# controller_board3.net
KiCad netlist of a schematic drawn in EAGLE
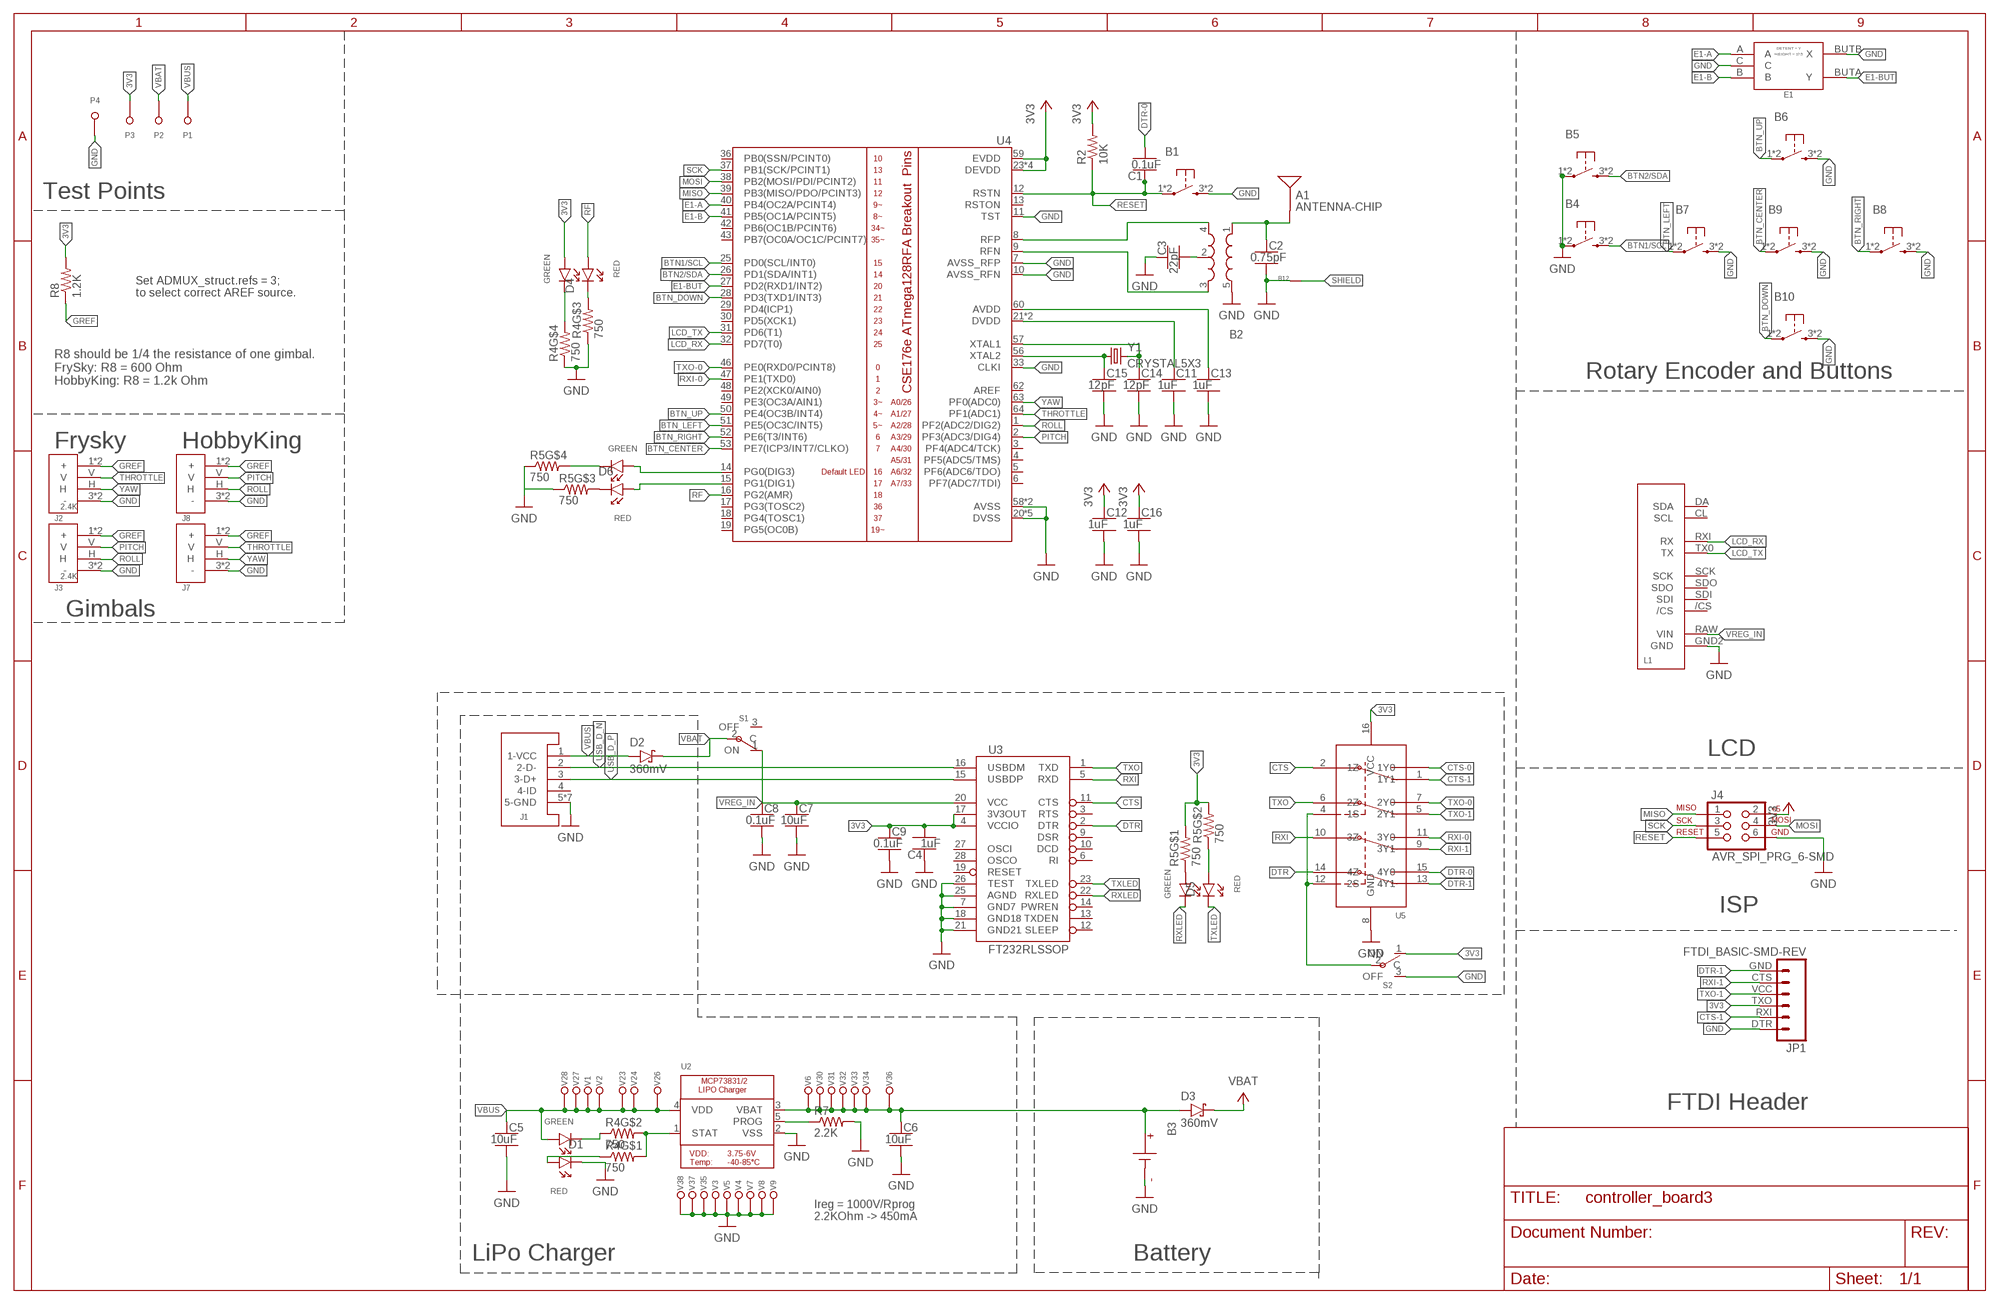
[diagram p0: schematic, sheet 1]

(export (version "E")
  (design (tool "Eeschema 10.0.6"))
  (components
    (comp (ref "A1")
      (value "ANTENNA-CHIP")
      (footprint "eagle-import:ANTENNA-CHIP")
      (fields
        (field (name "MFR") "Linx Technologies Inc.")
        (field (name "MPN") "ANT-2.45-CHP-T")
        (field (name "CREATOR") "Swanson")
        (field (name "REVIEWER") "Swanson")
      )
      (libsource (lib "eagle-import") (part "ANTENNA-CHIP"))
    )
    (comp (ref "B1")
      (value "PUSHBUTTON_-4.5X4.5")
      (footprint "eagle-import:4.5MM_TACTILE_SWITCH_TL3305AF160QG")
      (fields (field (name "CREATOR") "Swanson"))
      (libsource (lib "eagle-import") (part "PUSHBUTTON_-4.5X4.5"))
    )
    (comp (ref "B2")
      (value "BALUN0805")
      (footprint "eagle-import:BALUN")
      (fields
        (field (name "MFR") "Wurth Electronics Inc")
        (field (name "MPN") "748421245")
        (field (name "CREATOR") "Swanson")
        (field (name "REVIEWER") "Swanson")
      )
      (libsource (lib "eagle-import") (part "BALUN0805"))
    )
    (comp (ref "B3")
      (value "BATTERY")
      (footprint "eagle-import:BATTERY-TERMINALS")
      (fields (field (name "CREATOR") "Swanson"))
      (libsource (lib "eagle-import") (part "BATTERY"))
    )
    (comp (ref "B4")
      (value "PUSHBUTTON_-4.5X4.5")
      (footprint "eagle-import:4.5MM_TACTILE_SWITCH_TL3305AF160QG")
      (fields (field (name "CREATOR") "Swanson"))
      (libsource (lib "eagle-import") (part "PUSHBUTTON_-4.5X4.5"))
    )
    (comp (ref "B5")
      (value "PUSHBUTTON_-4.5X4.5")
      (footprint "eagle-import:4.5MM_TACTILE_SWITCH_TL3305AF160QG")
      (fields (field (name "CREATOR") "Swanson"))
      (libsource (lib "eagle-import") (part "PUSHBUTTON_-4.5X4.5"))
    )
    (comp (ref "B6")
      (value "PUSHBUTTON_-4.5X4.5")
      (footprint "eagle-import:4.5MM_TACTILE_SWITCH_TL3305AF160QG")
      (fields (field (name "CREATOR") "Swanson"))
      (libsource (lib "eagle-import") (part "PUSHBUTTON_-4.5X4.5"))
    )
    (comp (ref "B7")
      (value "PUSHBUTTON_-4.5X4.5")
      (footprint "eagle-import:4.5MM_TACTILE_SWITCH_TL3305AF160QG")
      (fields (field (name "CREATOR") "Swanson"))
      (libsource (lib "eagle-import") (part "PUSHBUTTON_-4.5X4.5"))
    )
    (comp (ref "B8")
      (value "PUSHBUTTON_-4.5X4.5")
      (footprint "eagle-import:4.5MM_TACTILE_SWITCH_TL3305AF160QG")
      (fields (field (name "CREATOR") "Swanson"))
      (libsource (lib "eagle-import") (part "PUSHBUTTON_-4.5X4.5"))
    )
    (comp (ref "B9")
      (value "PUSHBUTTON_-4.5X4.5")
      (footprint "eagle-import:4.5MM_TACTILE_SWITCH_TL3305AF160QG")
      (fields (field (name "CREATOR") "Swanson"))
      (libsource (lib "eagle-import") (part "PUSHBUTTON_-4.5X4.5"))
    )
    (comp (ref "B10")
      (value "PUSHBUTTON_-4.5X4.5")
      (footprint "eagle-import:4.5MM_TACTILE_SWITCH_TL3305AF160QG")
      (fields (field (name "CREATOR") "Swanson"))
      (libsource (lib "eagle-import") (part "PUSHBUTTON_-4.5X4.5"))
    )
    (comp (ref "B12")
      (value "NET_BRIDGE")
      (footprint "eagle-import:NET_BRIDGE")
      (fields (field (name "CREATOR") "Michael Gonzalez"))
      (libsource (lib "eagle-import") (part "NET_BRIDGE"))
    )
    (comp (ref "C1")
      (value "0.1uF")
      (footprint "eagle-import:CAPC2012X140_HS")
      (fields
        (field (name "MFR") "TDK")
        (field (name "MPN") "C2012X7R2A104K125AA")
        (field (name "CREATOR") "Swanson")
        (field (name "REVIEWER") "Swanson")
      )
      (libsource (lib "eagle-import") (part "CAPACITOR-NP_SMD-2012-0805_CERAMIC-0.1UF"))
    )
    (comp (ref "C2")
      (value "0.75pF")
      (footprint "eagle-import:CAPC2012X140_HS")
      (fields
        (field (name "MFR") "Murata Electronics North America")
        (field (name "MPN") "GQM2195C2AR75CB01D")
        (field (name "CREATOR") "Swanson")
        (field (name "REVIEWER") "Swanson")
      )
      (libsource (lib "eagle-import") (part "CAPACITOR-NP_SMD-2012-0805_CERAMIC-0.75PF"))
    )
    (comp (ref "C3")
      (value "22pF")
      (footprint "eagle-import:CAPC2012X140_HS")
      (fields
        (field (name "MFR") "Murata Electronics North America")
        (field (name "MPN") "GRM21A5C2E220JW01D")
        (field (name "CREATOR") "Swanson")
        (field (name "REVIEWER") "Swanson")
      )
      (libsource (lib "eagle-import") (part "CAPACITOR-NP_SMD-2012-0805_CERAMIC-22PF"))
    )
    (comp (ref "C4")
      (value "1uF")
      (footprint "eagle-import:CAPC2012X140_HS")
      (fields
        (field (name "MFR") "Taiyo Yuden")
        (field (name "MPN") "TMK212B7105KG-T")
        (field (name "CREATOR") "Swanson")
        (field (name "REVIEWER") "Swanson")
      )
      (libsource (lib "eagle-import") (part "CAPACITOR-NP_SMD-2012-0805_CERAMIC-1UF"))
    )
    (comp (ref "C5")
      (value "10uF")
      (footprint "eagle-import:CAPC1608X100")
      (fields (field (name "CREATOR") "Swanson"))
      (libsource (lib "eagle-import") (part "CAPACITOR-NP_SMD-0603_CERAMIC-10UF"))
    )
    (comp (ref "C6")
      (value "10uF")
      (footprint "eagle-import:CAPC1608X100")
      (fields (field (name "CREATOR") "Swanson"))
      (libsource (lib "eagle-import") (part "CAPACITOR-NP_SMD-0603_CERAMIC-10UF"))
    )
    (comp (ref "C7")
      (value "10uF")
      (footprint "eagle-import:CAPC1608X100")
      (fields (field (name "CREATOR") "Swanson"))
      (libsource (lib "eagle-import") (part "CAPACITOR-NP_SMD-0603_CERAMIC-10UF"))
    )
    (comp (ref "C8")
      (value "0.1uF")
      (footprint "eagle-import:CAPC2012X140_HS")
      (fields
        (field (name "MFR") "TDK")
        (field (name "MPN") "C2012X7R2A104K125AA")
        (field (name "CREATOR") "Swanson")
        (field (name "REVIEWER") "Swanson")
      )
      (libsource (lib "eagle-import") (part "CAPACITOR-NP_SMD-2012-0805_CERAMIC-0.1UF"))
    )
    (comp (ref "C9")
      (value "0.1uF")
      (footprint "eagle-import:CAPC2012X140_HS")
      (fields
        (field (name "MFR") "TDK")
        (field (name "MPN") "C2012X7R2A104K125AA")
        (field (name "CREATOR") "Swanson")
        (field (name "REVIEWER") "Swanson")
      )
      (libsource (lib "eagle-import") (part "CAPACITOR-NP_SMD-2012-0805_CERAMIC-0.1UF"))
    )
    (comp (ref "C11")
      (value "1uF")
      (footprint "eagle-import:CAPC2012X140_HS")
      (fields
        (field (name "MFR") "Taiyo Yuden")
        (field (name "MPN") "TMK212B7105KG-T")
        (field (name "CREATOR") "Swanson")
        (field (name "REVIEWER") "Swanson")
      )
      (libsource (lib "eagle-import") (part "CAPACITOR-NP_SMD-2012-0805_CERAMIC-1UF"))
    )
    (comp (ref "C12")
      (value "1uF")
      (footprint "eagle-import:CAPC2012X140_HS")
      (fields
        (field (name "MFR") "Taiyo Yuden")
        (field (name "MPN") "TMK212B7105KG-T")
        (field (name "CREATOR") "Swanson")
        (field (name "REVIEWER") "Swanson")
      )
      (libsource (lib "eagle-import") (part "CAPACITOR-NP_SMD-2012-0805_CERAMIC-1UF"))
    )
    (comp (ref "C13")
      (value "1uF")
      (footprint "eagle-import:CAPC2012X140_HS")
      (fields
        (field (name "MFR") "Taiyo Yuden")
        (field (name "MPN") "TMK212B7105KG-T")
        (field (name "CREATOR") "Swanson")
        (field (name "REVIEWER") "Swanson")
      )
      (libsource (lib "eagle-import") (part "CAPACITOR-NP_SMD-2012-0805_CERAMIC-1UF"))
    )
    (comp (ref "C14")
      (value "12pF")
      (footprint "eagle-import:CAPC2012X140_HS")
      (fields
        (field (name "MFR") "Murata Electronics North America")
        (field (name "MPN") "GRM21A5C2E120JW01D")
        (field (name "CREATOR") "Swanson")
        (field (name "REVIEWER") "Swanson")
      )
      (libsource (lib "eagle-import") (part "CAPACITOR-NP_SMD-2012-0805_CERAMIC-12PF"))
    )
    (comp (ref "C15")
      (value "12pF")
      (footprint "eagle-import:CAPC2012X140_HS")
      (fields
        (field (name "MFR") "Murata Electronics North America")
        (field (name "MPN") "GRM21A5C2E120JW01D")
        (field (name "CREATOR") "Swanson")
        (field (name "REVIEWER") "Swanson")
      )
      (libsource (lib "eagle-import") (part "CAPACITOR-NP_SMD-2012-0805_CERAMIC-12PF"))
    )
    (comp (ref "C16")
      (value "1uF")
      (footprint "eagle-import:CAPC2012X140_HS")
      (fields
        (field (name "MFR") "Taiyo Yuden")
        (field (name "MPN") "TMK212B7105KG-T")
        (field (name "CREATOR") "Swanson")
        (field (name "REVIEWER") "Swanson")
      )
      (libsource (lib "eagle-import") (part "CAPACITOR-NP_SMD-2012-0805_CERAMIC-1UF"))
    )
    (comp (ref "D1")
      (value "LED-2X-GREEN/RED-1.6X1.5MM")
      (footprint "eagle-import:LED-2X-LITE-ON-1.6MMX1.5MM")
      (fields
        (field (name "COLOR2") "RED")
        (field (name "COLOR1") "GREEN")
        (field (name "CREATOR") "Swanson")
      )
      (libsource (lib "eagle-import") (part "LED-2X-GREEN/RED-1.6X1.5MM"))
    )
    (comp (ref "D2")
      (value "360mV")
      (footprint "eagle-import:SOD3716X135_HS")
      (fields
        (field (name "MFR") "Toshiba Semiconductor and Storage")
        (field (name "MPN") "CRS08(TE85L,Q,M)")
        (field (name "CREATOR") "Swanson")
        (field (name "REVIEWER") "Swanson")
      )
      (libsource (lib "eagle-import") (part "DIODE-SCHOTTKY_SMD-SOD123-360MV"))
    )
    (comp (ref "D3")
      (value "360mV")
      (footprint "eagle-import:SOD3716X135_HS")
      (fields
        (field (name "MFR") "Toshiba Semiconductor and Storage")
        (field (name "MPN") "CRS08(TE85L,Q,M)")
        (field (name "CREATOR") "Swanson")
        (field (name "REVIEWER") "Swanson")
      )
      (libsource (lib "eagle-import") (part "DIODE-SCHOTTKY_SMD-SOD123-360MV"))
    )
    (comp (ref "D4")
      (value "LED-2X-GREEN/RED-1.6X1.5MM")
      (footprint "eagle-import:LED-2X-LITE-ON-1.6MMX1.5MM")
      (fields
        (field (name "COLOR2") "RED")
        (field (name "COLOR1") "GREEN")
        (field (name "CREATOR") "Swanson")
      )
      (libsource (lib "eagle-import") (part "LED-2X-GREEN/RED-1.6X1.5MM"))
    )
    (comp (ref "D5")
      (value "LED-2X-GREEN/RED-1.6X1.5MM")
      (footprint "eagle-import:LED-2X-LITE-ON-1.6MMX1.5MM")
      (fields
        (field (name "COLOR2") "RED")
        (field (name "COLOR1") "GREEN")
        (field (name "CREATOR") "Swanson")
      )
      (libsource (lib "eagle-import") (part "LED-2X-GREEN/RED-1.6X1.5MM"))
    )
    (comp (ref "D6")
      (value "LED-2X-GREEN/RED-1.6X1.5MM")
      (footprint "eagle-import:LED-2X-LITE-ON-1.6MMX1.5MM")
      (fields
        (field (name "COLOR2") "RED")
        (field (name "COLOR1") "GREEN")
        (field (name "CREATOR") "Swanson")
      )
      (libsource (lib "eagle-import") (part "LED-2X-GREEN/RED-1.6X1.5MM"))
    )
    (comp (ref "E1")
      (value "ROTARY-ENCODER-W/BUTTON-BOURNS-PEC12R-4217F")
      (footprint "eagle-import:BOURNS-PEC12R")
      (fields (field (name "DETENT") "Y") (field (name "HEIGHT") "17.5") (field (name "CREATOR") "Swanson"))
      (libsource (lib "eagle-import") (part "ROTARY-ENCODER-W/BUTTON-BOURNS-PEC12R-4217F"))
    )
    (comp (ref "J1")
      (value "USB-MICROA-AMPHENOL-10118192-0001LF")
      (footprint "eagle-import:USB-MICROA-10118192-0001LF")
      (fields (field (name "CREATOR") "Swanson"))
      (libsource (lib "eagle-import") (part "USB-MICROA-AMPHENOL-10118192-0001LF"))
    )
    (comp (ref "J2")
      (value "2.4K")
      (footprint "eagle-import:JST-13-PTH")
      (fields (field (name "CREATOR") "Swanson"))
      (libsource (lib "eagle-import") (part "FRSKY-GIMBAL-FRYSKY"))
    )
    (comp (ref "J3")
      (value "2.4K")
      (footprint "eagle-import:JST-13-PTH")
      (fields (field (name "SPICEPREFIX") "E") (field (name "CREATOR") "Swanson"))
      (libsource (lib "eagle-import") (part "FRSKY-GIMBAL-FRYSKY"))
    )
    (comp (ref "J4")
      (value "AVR_SPI_PRG_6-SMD")
      (footprint "eagle-import:2X3-SMD")
      (fields (field (name "CREATOR") "Swanson"))
      (libsource (lib "eagle-import") (part "AVR_SPI_PRG_6-SMD"))
    )
    (comp (ref "J7")
      (value "FRSKY-GIMBAL-2X-SERVO-SMD")
      (footprint "eagle-import:2X-SERVO-SMD")
      (libsource (lib "eagle-import") (part "FRSKY-GIMBAL-2X-SERVO-SMD"))
    )
    (comp (ref "J8")
      (value "FRSKY-GIMBAL-2X-SERVO-SMD")
      (footprint "eagle-import:2X-SERVO-SMD")
      (libsource (lib "eagle-import") (part "FRSKY-GIMBAL-2X-SERVO-SMD"))
    )
    (comp (ref "JP1")
      (value "FTDI_BASIC-SMD-REV")
      (footprint "eagle-import:FTDI-BASIC-SMD")
      (libsource (lib "eagle-import") (part "FTDI_BASIC-SMD-REV"))
    )
    (comp (ref "L1")
      (value "SPARKFUN_SERLCD_SERIAL_REDUCED-SMD")
      (footprint "eagle-import:SPARKFUN_SERLCD_16X2_REDUCED_SMD")
      (fields (field (name "CREATOR") "Swanson"))
      (libsource (lib "eagle-import") (part "SPARKFUN_SERLCD_SERIAL_REDUCED-SMD"))
    )
    (comp (ref "P1")
      (value "TEST-POINT")
      (footprint "eagle-import:TEST-POINT-KEYSTONE-5000")
      (fields (field (name "CREATOR") "Swanson"))
      (libsource (lib "eagle-import") (part "TEST-POINT"))
    )
    (comp (ref "P2")
      (value "TEST-POINT")
      (footprint "eagle-import:TEST-POINT-KEYSTONE-5000")
      (fields (field (name "CREATOR") "Swanson"))
      (libsource (lib "eagle-import") (part "TEST-POINT"))
    )
    (comp (ref "P3")
      (value "TEST-POINT")
      (footprint "eagle-import:TEST-POINT-KEYSTONE-5000")
      (fields (field (name "CREATOR") "Swanson"))
      (libsource (lib "eagle-import") (part "TEST-POINT"))
    )
    (comp (ref "P4")
      (value "TEST-POINT")
      (footprint "eagle-import:TEST-POINT-KEYSTONE-5000")
      (fields (field (name "CREATOR") "Swanson"))
      (libsource (lib "eagle-import") (part "TEST-POINT"))
    )
    (comp (ref "R2")
      (value "10K")
      (footprint "eagle-import:RESC2012X60_HS")
      (fields
        (field (name "MFR") "Yageo")
        (field (name "MPN") "RC0805JR-0710KL")
        (field (name "CREATOR") "Swanson")
        (field (name "REVIEWER") "Swanson")
      )
      (libsource (lib "eagle-import") (part "RESISTOR_SMD-2012-0805-10K"))
    )
    (comp (ref "R4")
      (value "750")
      (footprint "eagle-import:RESCAXS50P200X100X45-8")
      (fields (field (name "CREATOR") "Swanson"))
      (libsource (lib "eagle-import") (part "RESISTOR-PACK-4X-750"))
    )
    (comp (ref "R5")
      (value "750")
      (footprint "eagle-import:RESCAXS50P200X100X45-8")
      (fields (field (name "CREATOR") "Swanson"))
      (libsource (lib "eagle-import") (part "RESISTOR-PACK-4X-750"))
    )
    (comp (ref "R7")
      (value "2.2K")
      (footprint "eagle-import:RESC2012X60_HS")
      (fields (field (name "CREATOR") "SWANSON"))
      (libsource (lib "eagle-import") (part "RESISTOR_SMD-2012-0805-2.2K"))
    )
    (comp (ref "R8")
      (value "1.2K")
      (footprint "eagle-import:RESC2012X60_HS")
      (fields (field (name "CREATOR") "Swanson"))
      (libsource (lib "eagle-import") (part "RESISTOR_SMD-2012-0805-1.2K"))
    )
    (comp (ref "S1")
      (value "POWER-SWITCH-MFS201N-9-Z-SMD-VERTICAL")
      (footprint "eagle-import:JS102011JCQN")
      (fields (field (name "CREATOR") "Swanson"))
      (libsource (lib "eagle-import") (part "POWER-SWITCH-MFS201N-9-Z-SMD-VERTICAL"))
    )
    (comp (ref "S2")
      (value "POWER-SWITCH-MFS201N-9-Z-SMD-VERTICAL")
      (footprint "eagle-import:JS102011JCQN")
      (fields (field (name "CREATOR") "Swanson"))
      (libsource (lib "eagle-import") (part "POWER-SWITCH-MFS201N-9-Z-SMD-VERTICAL"))
    )
    (comp (ref "U2")
      (value "MCP73831T-2ACI/OT")
      (footprint "eagle-import:SOT23-5")
      (fields (field (name "CREATOR") "Adafruit"))
      (libsource (lib "eagle-import") (part "MCP73831/2"))
    )
    (comp (ref "U3")
      (value "FT232RLSSOP")
      (footprint "eagle-import:SSOP28DB")
      (fields (field (name "CREATOR") "Swanson"))
      (libsource (lib "eagle-import") (part "FT232RLSSOP"))
    )
    (comp (ref "U4")
      (value "ATMEGA128RFA1")
      (footprint "eagle-import:QFN-64")
      (fields
        (field (name "MFR") "Atmel")
        (field (name "MPN") "ATMEGA128RFA1-ZUR00")
        (field (name "CREATOR") "Swanson")
        (field (name "REVIEWER") "Swanson")
      )
      (libsource (lib "eagle-import") (part "ATMEGA128RFA1"))
    )
    (comp (ref "U5")
      (value "DPDT-X2")
      (footprint "eagle-import:SOP65P640X110-16")
      (fields (field (name "CREATOR") "Swanson"))
      (libsource (lib "eagle-import") (part "DPDT-X2"))
    )
    (comp (ref "V1")
      (value "LOCKED-VIA-0.2")
      (footprint "eagle-import:VIA-0.2MM")
      (fields (field (name "CREATOR") "Swanson"))
      (libsource (lib "eagle-import") (part "LOCKED-VIA-0.2"))
    )
    (comp (ref "V2")
      (value "LOCKED-VIA-0.2")
      (footprint "eagle-import:VIA-0.2MM")
      (fields (field (name "CREATOR") "Swanson"))
      (libsource (lib "eagle-import") (part "LOCKED-VIA-0.2"))
    )
    (comp (ref "V3")
      (value "LOCKED-VIA-0.2")
      (footprint "eagle-import:VIA-0.2MM")
      (fields (field (name "CREATOR") "Swanson"))
      (libsource (lib "eagle-import") (part "LOCKED-VIA-0.2"))
    )
    (comp (ref "V4")
      (value "LOCKED-VIA-0.2")
      (footprint "eagle-import:VIA-0.2MM")
      (fields (field (name "CREATOR") "Swanson"))
      (libsource (lib "eagle-import") (part "LOCKED-VIA-0.2"))
    )
    (comp (ref "V5")
      (value "LOCKED-VIA-0.2")
      (footprint "eagle-import:VIA-0.2MM")
      (fields (field (name "CREATOR") "Swanson"))
      (libsource (lib "eagle-import") (part "LOCKED-VIA-0.2"))
    )
    (comp (ref "V6")
      (value "LOCKED-VIA-0.2")
      (footprint "eagle-import:VIA-0.2MM")
      (fields (field (name "CREATOR") "Swanson"))
      (libsource (lib "eagle-import") (part "LOCKED-VIA-0.2"))
    )
    (comp (ref "V7")
      (value "LOCKED-VIA-0.2")
      (footprint "eagle-import:VIA-0.2MM")
      (fields (field (name "CREATOR") "Swanson"))
      (libsource (lib "eagle-import") (part "LOCKED-VIA-0.2"))
    )
    (comp (ref "V8")
      (value "LOCKED-VIA-0.2")
      (footprint "eagle-import:VIA-0.2MM")
      (fields (field (name "CREATOR") "Swanson"))
      (libsource (lib "eagle-import") (part "LOCKED-VIA-0.2"))
    )
    (comp (ref "V9")
      (value "LOCKED-VIA-0.2")
      (footprint "eagle-import:VIA-0.2MM")
      (fields (field (name "CREATOR") "Swanson"))
      (libsource (lib "eagle-import") (part "LOCKED-VIA-0.2"))
    )
    (comp (ref "V23")
      (value "LOCKED-VIA-0.2")
      (footprint "eagle-import:VIA-0.2MM")
      (fields (field (name "CREATOR") "Swanson"))
      (libsource (lib "eagle-import") (part "LOCKED-VIA-0.2"))
    )
    (comp (ref "V24")
      (value "LOCKED-VIA-0.2")
      (footprint "eagle-import:VIA-0.2MM")
      (fields (field (name "CREATOR") "Swanson"))
      (libsource (lib "eagle-import") (part "LOCKED-VIA-0.2"))
    )
    (comp (ref "V26")
      (value "LOCKED-VIA-0.2")
      (footprint "eagle-import:VIA-0.2MM")
      (fields (field (name "CREATOR") "Swanson"))
      (libsource (lib "eagle-import") (part "LOCKED-VIA-0.2"))
    )
    (comp (ref "V27")
      (value "LOCKED-VIA-0.2")
      (footprint "eagle-import:VIA-0.2MM")
      (fields (field (name "CREATOR") "Swanson"))
      (libsource (lib "eagle-import") (part "LOCKED-VIA-0.2"))
    )
    (comp (ref "V28")
      (value "LOCKED-VIA-0.2")
      (footprint "eagle-import:VIA-0.2MM")
      (fields (field (name "CREATOR") "Swanson"))
      (libsource (lib "eagle-import") (part "LOCKED-VIA-0.2"))
    )
    (comp (ref "V30")
      (value "LOCKED-VIA-0.2")
      (footprint "eagle-import:VIA-0.2MM")
      (fields (field (name "CREATOR") "Swanson"))
      (libsource (lib "eagle-import") (part "LOCKED-VIA-0.2"))
    )
    (comp (ref "V31")
      (value "LOCKED-VIA-0.2")
      (footprint "eagle-import:VIA-0.2MM")
      (fields (field (name "CREATOR") "Swanson"))
      (libsource (lib "eagle-import") (part "LOCKED-VIA-0.2"))
    )
    (comp (ref "V32")
      (value "LOCKED-VIA-0.2")
      (footprint "eagle-import:VIA-0.2MM")
      (fields (field (name "CREATOR") "Swanson"))
      (libsource (lib "eagle-import") (part "LOCKED-VIA-0.2"))
    )
    (comp (ref "V33")
      (value "LOCKED-VIA-0.2")
      (footprint "eagle-import:VIA-0.2MM")
      (fields (field (name "CREATOR") "Swanson"))
      (libsource (lib "eagle-import") (part "LOCKED-VIA-0.2"))
    )
    (comp (ref "V34")
      (value "LOCKED-VIA-0.2")
      (footprint "eagle-import:VIA-0.2MM")
      (fields (field (name "CREATOR") "Swanson"))
      (libsource (lib "eagle-import") (part "LOCKED-VIA-0.2"))
    )
    (comp (ref "V35")
      (value "LOCKED-VIA-0.2")
      (footprint "eagle-import:VIA-0.2MM")
      (fields (field (name "CREATOR") "Swanson"))
      (libsource (lib "eagle-import") (part "LOCKED-VIA-0.2"))
    )
    (comp (ref "V36")
      (value "LOCKED-VIA-0.2")
      (footprint "eagle-import:VIA-0.2MM")
      (fields (field (name "CREATOR") "Swanson"))
      (libsource (lib "eagle-import") (part "LOCKED-VIA-0.2"))
    )
    (comp (ref "V37")
      (value "LOCKED-VIA-0.2")
      (footprint "eagle-import:VIA-0.2MM")
      (fields (field (name "CREATOR") "Swanson"))
      (libsource (lib "eagle-import") (part "LOCKED-VIA-0.2"))
    )
    (comp (ref "V38")
      (value "LOCKED-VIA-0.2")
      (footprint "eagle-import:VIA-0.2MM")
      (fields (field (name "CREATOR") "Swanson"))
      (libsource (lib "eagle-import") (part "LOCKED-VIA-0.2"))
    )
    (comp (ref "Y1")
      (value "CRYSTAL5X3")
      (footprint "eagle-import:CRYSTAL-SMD-5X3")
      (fields
        (field (name "MFR") "Abracon LLC")
        (field (name "MPN") "ABM3B-16.000MHZ-B2-T")
        (field (name "CREATOR") "Swanson")
        (field (name "REVIEWER") "Swanson")
      )
      (libsource (lib "eagle-import") (part "CRYSTAL5X3"))
    )
  )
  (nets
    (net (code "1") (name "3V3") (class "Default")
      (node (ref "C12") (pin "1") (pinfunction "1_1") (pintype "passive"))
      (node (ref "C16") (pin "1") (pinfunction "1_1") (pintype "passive"))
      (node (ref "C4") (pin "2") (pinfunction "2_2") (pintype "passive"))
      (node (ref "C9") (pin "1") (pinfunction "1_1") (pintype "passive"))
      (node (ref "D4") (pin "A2") (pinfunction "A2_A2") (pintype "passive"))
      (node (ref "J4") (pin "2") (pinfunction "2_2") (pintype "passive"))
      (node (ref "JP1") (pin "TXO") (pinfunction "4_TXO") (pintype "passive"))
      (node (ref "P3") (pin "T") (pinfunction "T_T") (pintype "bidirectional"))
      (node (ref "R2") (pin "2") (pinfunction "2_2") (pintype "passive"))
      (node (ref "R5") (pin "5") (pinfunction "2_5") (pintype "passive"))
      (node (ref "R5") (pin "6") (pinfunction "2_6") (pintype "passive"))
      (node (ref "R8") (pin "2") (pinfunction "2_2") (pintype "passive"))
      (node (ref "S2") (pin "1") (pinfunction "ON_1") (pintype "bidirectional"))
      (node (ref "U3") (pin "17") (pinfunction "3V3OUT_17") (pintype "output"))
      (node (ref "U3") (pin "4") (pinfunction "VCCIO_4") (pintype "power_in"))
      (node (ref "U4") (pin "23") (pinfunction "DEVDD_23") (pintype "bidirectional"))
      (node (ref "U4") (pin "34") (pinfunction "DEVDD_34") (pintype "bidirectional"))
      (node (ref "U4") (pin "44") (pinfunction "DEVDD_44") (pintype "bidirectional"))
      (node (ref "U4") (pin "54") (pinfunction "DEVDD_54") (pintype "bidirectional"))
      (node (ref "U4") (pin "59") (pinfunction "EVDD_59") (pintype "bidirectional"))
      (node (ref "U5") (pin "16") (pinfunction "VCC_16") (pintype "bidirectional"))
    )
    (net (code "2") (name "BTN1{slash}SCL") (class "Default")
      (node (ref "B4") (pin "3") (pinfunction "2_3") (pintype "passive"))
      (node (ref "B4") (pin "4") (pinfunction "2_4") (pintype "passive"))
      (node (ref "U4") (pin "25") (pinfunction "PD0(SCL/INT0)_25") (pintype "bidirectional"))
    )
    (net (code "3") (name "BTN2{slash}SDA") (class "Default")
      (node (ref "B5") (pin "3") (pinfunction "2_3") (pintype "passive"))
      (node (ref "B5") (pin "4") (pinfunction "2_4") (pintype "passive"))
      (node (ref "U4") (pin "26") (pinfunction "PD1(SDA/INT1)_26") (pintype "bidirectional"))
    )
    (net (code "4") (name "BTN_CENTER") (class "Default")
      (node (ref "B9") (pin "1") (pinfunction "1_1") (pintype "passive"))
      (node (ref "B9") (pin "2") (pinfunction "1_2") (pintype "passive"))
      (node (ref "U4") (pin "53") (pinfunction "PE7(ICP3/INT7/CLKO)_53") (pintype "bidirectional"))
    )
    (net (code "5") (name "BTN_DOWN") (class "Default")
      (node (ref "B10") (pin "1") (pinfunction "1_1") (pintype "passive"))
      (node (ref "B10") (pin "2") (pinfunction "1_2") (pintype "passive"))
      (node (ref "U4") (pin "28") (pinfunction "PD3(TXD1/INT3)_28") (pintype "bidirectional"))
    )
    (net (code "6") (name "BTN_LEFT") (class "Default")
      (node (ref "B7") (pin "1") (pinfunction "1_1") (pintype "passive"))
      (node (ref "B7") (pin "2") (pinfunction "1_2") (pintype "passive"))
      (node (ref "U4") (pin "51") (pinfunction "PE5(OC3C/INT5)_51") (pintype "bidirectional"))
    )
    (net (code "7") (name "BTN_RIGHT") (class "Default")
      (node (ref "B8") (pin "1") (pinfunction "1_1") (pintype "passive"))
      (node (ref "B8") (pin "2") (pinfunction "1_2") (pintype "passive"))
      (node (ref "U4") (pin "52") (pinfunction "PE6(T3/INT6)_52") (pintype "bidirectional"))
    )
    (net (code "8") (name "BTN_UP") (class "Default")
      (node (ref "B6") (pin "1") (pinfunction "1_1") (pintype "passive"))
      (node (ref "B6") (pin "2") (pinfunction "1_2") (pintype "passive"))
      (node (ref "U4") (pin "50") (pinfunction "PE4(OC3B/INT4)_50") (pintype "bidirectional"))
    )
    (net (code "9") (name "CTS") (class "Default")
      (node (ref "U3") (pin "11") (pinfunction "CTS_11") (pintype "input"))
      (node (ref "U5") (pin "2") (pinfunction "1Z_2") (pintype "bidirectional"))
    )
    (net (code "10") (name "CTS-0") (class "Default")
      (node (ref "U5") (pin "3") (pinfunction "1Y0_3") (pintype "bidirectional"))
    )
    (net (code "11") (name "CTS-1") (class "Default")
      (node (ref "JP1") (pin "RXI") (pinfunction "5_RXI") (pintype "passive"))
      (node (ref "U5") (pin "1") (pinfunction "1Y1_1") (pintype "bidirectional"))
    )
    (net (code "12") (name "DTR") (class "Default")
      (node (ref "U3") (pin "2") (pinfunction "DTR_2") (pintype "output"))
      (node (ref "U5") (pin "14") (pinfunction "4Z_14") (pintype "bidirectional"))
    )
    (net (code "13") (name "DTR-0") (class "Default")
      (node (ref "C1") (pin "2") (pinfunction "2_2") (pintype "passive"))
      (node (ref "U5") (pin "15") (pinfunction "4Y0_15") (pintype "bidirectional"))
    )
    (net (code "14") (name "DTR-1") (class "Default")
      (node (ref "JP1") (pin "GND") (pinfunction "1_GND") (pintype "passive"))
      (node (ref "U5") (pin "13") (pinfunction "4Y1_13") (pintype "bidirectional"))
    )
    (net (code "15") (name "E1-A") (class "Default")
      (node (ref "E1") (pin "A") (pinfunction "A_A") (pintype "bidirectional"))
      (node (ref "U4") (pin "40") (pinfunction "PB4(OC2A/PCINT4)_40") (pintype "bidirectional"))
    )
    (net (code "16") (name "E1-B") (class "Default")
      (node (ref "E1") (pin "B") (pinfunction "B_B") (pintype "bidirectional"))
      (node (ref "U4") (pin "41") (pinfunction "PB5(OC1A/PCINT5)_41") (pintype "bidirectional"))
    )
    (net (code "17") (name "E1-BUT") (class "Default")
      (node (ref "E1") (pin "BUTA") (pinfunction "Y_BUTA") (pintype "bidirectional"))
      (node (ref "U4") (pin "27") (pinfunction "PD2(RXD1/INT2)_27") (pintype "bidirectional"))
    )
    (net (code "18") (name "GND") (class "Default")
      (node (ref "B1") (pin "3") (pinfunction "2_3") (pintype "passive"))
      (node (ref "B1") (pin "4") (pinfunction "2_4") (pintype "passive"))
      (node (ref "B10") (pin "3") (pinfunction "2_3") (pintype "passive"))
      (node (ref "B10") (pin "4") (pinfunction "2_4") (pintype "passive"))
      (node (ref "B12") (pin "P1") (pinfunction "P1_P1") (pintype "bidirectional"))
      (node (ref "B2") (pin "5") (pinfunction "GND_5") (pintype "bidirectional"))
      (node (ref "B3") (pin "-") (pinfunction "N_-") (pintype "bidirectional"))
      (node (ref "B4") (pin "1") (pinfunction "1_1") (pintype "passive"))
      (node (ref "B4") (pin "2") (pinfunction "1_2") (pintype "passive"))
      (node (ref "B5") (pin "1") (pinfunction "1_1") (pintype "passive"))
      (node (ref "B5") (pin "2") (pinfunction "1_2") (pintype "passive"))
      (node (ref "B6") (pin "3") (pinfunction "2_3") (pintype "passive"))
      (node (ref "B6") (pin "4") (pinfunction "2_4") (pintype "passive"))
      (node (ref "B7") (pin "3") (pinfunction "2_3") (pintype "passive"))
      (node (ref "B7") (pin "4") (pinfunction "2_4") (pintype "passive"))
      (node (ref "B8") (pin "3") (pinfunction "2_3") (pintype "passive"))
      (node (ref "B8") (pin "4") (pinfunction "2_4") (pintype "passive"))
      (node (ref "B9") (pin "3") (pinfunction "2_3") (pintype "passive"))
      (node (ref "B9") (pin "4") (pinfunction "2_4") (pintype "passive"))
      (node (ref "C11") (pin "2") (pinfunction "2_2") (pintype "passive"))
      (node (ref "C12") (pin "2") (pinfunction "2_2") (pintype "passive"))
      (node (ref "C13") (pin "2") (pinfunction "2_2") (pintype "passive"))
      (node (ref "C14") (pin "2") (pinfunction "2_2") (pintype "passive"))
      (node (ref "C15") (pin "2") (pinfunction "2_2") (pintype "passive"))
      (node (ref "C16") (pin "2") (pinfunction "2_2") (pintype "passive"))
      (node (ref "C2") (pin "2") (pinfunction "2_2") (pintype "passive"))
      (node (ref "C3") (pin "1") (pinfunction "1_1") (pintype "passive"))
      (node (ref "C4") (pin "1") (pinfunction "1_1") (pintype "passive"))
      (node (ref "C5") (pin "2") (pinfunction "2_2") (pintype "passive"))
      (node (ref "C6") (pin "2") (pinfunction "2_2") (pintype "passive"))
      (node (ref "C7") (pin "2") (pinfunction "2_2") (pintype "passive"))
      (node (ref "C8") (pin "2") (pinfunction "2_2") (pintype "passive"))
      (node (ref "C9") (pin "2") (pinfunction "2_2") (pintype "passive"))
      (node (ref "D1") (pin "C1") (pinfunction "C1_C1") (pintype "passive"))
      (node (ref "E1") (pin "BUTB") (pinfunction "X_BUTB") (pintype "bidirectional"))
      (node (ref "E1") (pin "C") (pinfunction "C_C") (pintype "bidirectional"))
      (node (ref "J1") (pin "10") (pinfunction "5-GND_10") (pintype "bidirectional"))
      (node (ref "J1") (pin "11") (pinfunction "5-GND_11") (pintype "bidirectional"))
      (node (ref "J1") (pin "5") (pinfunction "5-GND_5") (pintype "bidirectional"))
      (node (ref "J1") (pin "6") (pinfunction "5-GND_6") (pintype "bidirectional"))
      (node (ref "J1") (pin "7") (pinfunction "5-GND_7") (pintype "bidirectional"))
      (node (ref "J1") (pin "8") (pinfunction "5-GND_8") (pintype "bidirectional"))
      (node (ref "J1") (pin "9") (pinfunction "5-GND_9") (pintype "bidirectional"))
      (node (ref "J2") (pin "3") (pinfunction "-_3") (pintype "bidirectional"))
      (node (ref "J2") (pin "6") (pinfunction "-_6") (pintype "bidirectional"))
      (node (ref "J3") (pin "3") (pinfunction "-_3") (pintype "bidirectional"))
      (node (ref "J3") (pin "6") (pinfunction "-_6") (pintype "bidirectional"))
      (node (ref "J4") (pin "6") (pinfunction "6_6") (pintype "passive"))
      (node (ref "J7") (pin "3") (pinfunction "-_3") (pintype "bidirectional"))
      (node (ref "J7") (pin "6") (pinfunction "-_6") (pintype "bidirectional"))
      (node (ref "J8") (pin "3") (pinfunction "-_3") (pintype "bidirectional"))
      (node (ref "J8") (pin "6") (pinfunction "-_6") (pintype "bidirectional"))
      (node (ref "JP1") (pin "DTR") (pinfunction "6_DTR") (pintype "passive"))
      (node (ref "L1") (pin "GND2") (pinfunction "GND_GND2") (pintype "bidirectional"))
      (node (ref "P4") (pin "T") (pinfunction "T_T") (pintype "bidirectional"))
      (node (ref "R4") (pin "1") (pinfunction "1_1") (pintype "passive"))
      (node (ref "R4") (pin "2") (pinfunction "1_2") (pintype "passive"))
      (node (ref "R5") (pin "1") (pinfunction "1_1") (pintype "passive"))
      (node (ref "R5") (pin "2") (pinfunction "1_2") (pintype "passive"))
      (node (ref "R7") (pin "2") (pinfunction "2_2") (pintype "passive"))
      (node (ref "S2") (pin "3") (pinfunction "OFF_3") (pintype "bidirectional"))
      (node (ref "U2") (pin "2") (pinfunction "VSS_2") (pintype "power_in"))
      (node (ref "U3") (pin "18") (pinfunction "GND18_18") (pintype "power_in"))
      (node (ref "U3") (pin "21") (pinfunction "GND21_21") (pintype "power_in"))
      (node (ref "U3") (pin "25") (pinfunction "AGND_25") (pintype "power_in"))
      (node (ref "U3") (pin "26") (pinfunction "TEST_26") (pintype "input"))
      (node (ref "U3") (pin "7") (pinfunction "GND7_7") (pintype "power_in"))
      (node (ref "U4") (pin "10") (pinfunction "AVSS_RFN_10") (pintype "bidirectional"))
      (node (ref "U4") (pin "11") (pinfunction "TST_11") (pintype "bidirectional"))
      (node (ref "U4") (pin "20") (pinfunction "DVSS_20") (pintype "bidirectional"))
      (node (ref "U4") (pin "24") (pinfunction "DVSS_24") (pintype "bidirectional"))
      (node (ref "U4") (pin "33") (pinfunction "CLKI_33") (pintype "bidirectional"))
      (node (ref "U4") (pin "35") (pinfunction "DVSS_35") (pintype "bidirectional"))
      (node (ref "U4") (pin "45") (pinfunction "DVSS_45") (pintype "bidirectional"))
      (node (ref "U4") (pin "55") (pinfunction "DVSS_55") (pintype "bidirectional"))
      (node (ref "U4") (pin "58") (pinfunction "AVSS_58") (pintype "bidirectional"))
      (node (ref "U4") (pin "61") (pinfunction "AVSS_61") (pintype "bidirectional"))
      (node (ref "U4") (pin "7") (pinfunction "AVSS_RFP_7") (pintype "bidirectional"))
      (node (ref "U5") (pin "8") (pinfunction "GND_8") (pintype "bidirectional"))
      (node (ref "V3") (pin "P1") (pinfunction "N_P1") (pintype "bidirectional"))
      (node (ref "V35") (pin "P1") (pinfunction "N_P1") (pintype "bidirectional"))
      (node (ref "V37") (pin "P1") (pinfunction "N_P1") (pintype "bidirectional"))
      (node (ref "V38") (pin "P1") (pinfunction "N_P1") (pintype "bidirectional"))
      (node (ref "V4") (pin "P1") (pinfunction "N_P1") (pintype "bidirectional"))
      (node (ref "V5") (pin "P1") (pinfunction "N_P1") (pintype "bidirectional"))
      (node (ref "V7") (pin "P1") (pinfunction "N_P1") (pintype "bidirectional"))
      (node (ref "V8") (pin "P1") (pinfunction "N_P1") (pintype "bidirectional"))
      (node (ref "V9") (pin "P1") (pinfunction "N_P1") (pintype "bidirectional"))
    )
    (net (code "19") (name "GREF") (class "Default")
      (node (ref "J2") (pin "1") (pinfunction "+_1") (pintype "bidirectional"))
      (node (ref "J2") (pin "4") (pinfunction "+_4") (pintype "bidirectional"))
      (node (ref "J3") (pin "1") (pinfunction "+_1") (pintype "bidirectional"))
      (node (ref "J3") (pin "4") (pinfunction "+_4") (pintype "bidirectional"))
      (node (ref "J7") (pin "1") (pinfunction "+_1") (pintype "bidirectional"))
      (node (ref "J7") (pin "4") (pinfunction "+_4") (pintype "bidirectional"))
      (node (ref "J8") (pin "1") (pinfunction "+_1") (pintype "bidirectional"))
      (node (ref "J8") (pin "4") (pinfunction "+_4") (pintype "bidirectional"))
      (node (ref "R8") (pin "1") (pinfunction "1_1") (pintype "passive"))
    )
    (net (code "20") (name "LCD_RX") (class "Default")
      (node (ref "L1") (pin "RXI") (pinfunction "RX_RXI") (pintype "bidirectional"))
      (node (ref "U4") (pin "32") (pinfunction "PD7(T0)_32") (pintype "bidirectional"))
    )
    (net (code "21") (name "LCD_TX") (class "Default")
      (node (ref "L1") (pin "TX0") (pinfunction "TX_TX0") (pintype "bidirectional"))
      (node (ref "U4") (pin "31") (pinfunction "PD6(T1)_31") (pintype "bidirectional"))
    )
    (net (code "22") (name "MISO") (class "Default")
      (node (ref "J4") (pin "1") (pinfunction "1_1") (pintype "passive"))
      (node (ref "U4") (pin "39") (pinfunction "PB3(MISO/PDO/PCINT3)_39") (pintype "bidirectional"))
    )
    (net (code "23") (name "MOSI") (class "Default")
      (node (ref "J4") (pin "4") (pinfunction "4_4") (pintype "passive"))
      (node (ref "U4") (pin "38") (pinfunction "PB2(MOSI/PDI/PCINT2)_38") (pintype "bidirectional"))
    )
    (net (code "24") (name "Net-(A1-SIGNAL)") (class "Default")
      (node (ref "A1") (pin "FEED") (pinfunction "SIGNAL_FEED") (pintype "bidirectional"))
      (node (ref "B2") (pin "1") (pinfunction "IN_1") (pintype "bidirectional"))
      (node (ref "C2") (pin "1") (pinfunction "1_1") (pintype "passive"))
    )
    (net (code "25") (name "Net-(B2-GND-Pad2)") (class "Default")
      (node (ref "B2") (pin "2") (pinfunction "GND_2") (pintype "bidirectional"))
      (node (ref "C3") (pin "2") (pinfunction "2_2") (pintype "passive"))
    )
    (net (code "26") (name "Net-(B2-OUT1)") (class "Default")
      (node (ref "B2") (pin "4") (pinfunction "OUT1_4") (pintype "bidirectional"))
      (node (ref "U4") (pin "8") (pinfunction "RFP_8") (pintype "bidirectional"))
    )
    (net (code "27") (name "Net-(B2-OUT2)") (class "Default")
      (node (ref "B2") (pin "3") (pinfunction "OUT2_3") (pintype "bidirectional"))
      (node (ref "U4") (pin "9") (pinfunction "RFN_9") (pintype "bidirectional"))
    )
    (net (code "28") (name "Net-(B3-P)") (class "Default")
      (node (ref "B3") (pin "+") (pinfunction "P_+") (pintype "bidirectional"))
      (node (ref "C6") (pin "1") (pinfunction "1_1") (pintype "passive"))
      (node (ref "D3") (pin "A") (pinfunction "A_A") (pintype "passive"))
      (node (ref "U2") (pin "3") (pinfunction "VBAT_3") (pintype "power_in"))
      (node (ref "V30") (pin "P1") (pinfunction "N_P1") (pintype "bidirectional"))
      (node (ref "V31") (pin "P1") (pinfunction "N_P1") (pintype "bidirectional"))
      (node (ref "V32") (pin "P1") (pinfunction "N_P1") (pintype "bidirectional"))
      (node (ref "V33") (pin "P1") (pinfunction "N_P1") (pintype "bidirectional"))
      (node (ref "V34") (pin "P1") (pinfunction "N_P1") (pintype "bidirectional"))
      (node (ref "V36") (pin "P1") (pinfunction "N_P1") (pintype "bidirectional"))
      (node (ref "V6") (pin "P1") (pinfunction "N_P1") (pintype "bidirectional"))
    )
    (net (code "29") (name "Net-(C11-Pad1)") (class "Default")
      (node (ref "C11") (pin "1") (pinfunction "1_1") (pintype "passive"))
      (node (ref "U4") (pin "21") (pinfunction "DVDD_21") (pintype "bidirectional"))
      (node (ref "U4") (pin "22") (pinfunction "DVDD_22") (pintype "bidirectional"))
    )
    (net (code "30") (name "Net-(R4A-1)") (class "Default")
      (node (ref "D1") (pin "A1") (pinfunction "A1_A1") (pintype "passive"))
      (node (ref "R4") (pin "4") (pinfunction "1_4") (pintype "passive"))
    )
    (net (code "31") (name "Net-(R4A-2)") (class "Default")
      (node (ref "R4") (pin "5") (pinfunction "2_5") (pintype "passive"))
      (node (ref "R4") (pin "6") (pinfunction "2_6") (pintype "passive"))
      (node (ref "U2") (pin "1") (pinfunction "STAT_1") (pintype "output"))
    )
    (net (code "32") (name "Net-(R4B-1)") (class "Default")
      (node (ref "D1") (pin "C2") (pinfunction "C2_C2") (pintype "passive"))
      (node (ref "R4") (pin "3") (pinfunction "1_3") (pintype "passive"))
    )
    (net (code "33") (name "Net-(R4C-2)") (class "Default")
      (node (ref "D4") (pin "C1") (pinfunction "C1_C1") (pintype "passive"))
      (node (ref "R4") (pin "7") (pinfunction "2_7") (pintype "passive"))
    )
    (net (code "34") (name "Net-(R4D-2)") (class "Default")
      (node (ref "D4") (pin "C2") (pinfunction "C2_C2") (pintype "passive"))
      (node (ref "R4") (pin "8") (pinfunction "2_8") (pintype "passive"))
    )
    (net (code "35") (name "Net-(R5A-1)") (class "Default")
      (node (ref "D5") (pin "A2") (pinfunction "A2_A2") (pintype "passive"))
      (node (ref "R5") (pin "4") (pinfunction "1_4") (pintype "passive"))
    )
    (net (code "36") (name "Net-(R5B-1)") (class "Default")
      (node (ref "D5") (pin "A1") (pinfunction "A1_A1") (pintype "passive"))
      (node (ref "R5") (pin "3") (pinfunction "1_3") (pintype "passive"))
    )
    (net (code "37") (name "Net-(R5C-2)") (class "Default")
      (node (ref "D6") (pin "C1") (pinfunction "C1_C1") (pintype "passive"))
      (node (ref "R5") (pin "7") (pinfunction "2_7") (pintype "passive"))
    )
    (net (code "38") (name "Net-(R5D-2)") (class "Default")
      (node (ref "D6") (pin "C2") (pinfunction "C2_C2") (pintype "passive"))
      (node (ref "R5") (pin "8") (pinfunction "2_8") (pintype "passive"))
    )
    (net (code "39") (name "Net-(S2-C)") (class "Default")
      (node (ref "S2") (pin "2") (pinfunction "C_2") (pintype "bidirectional"))
      (node (ref "U5") (pin "12") (pinfunction "2S_12") (pintype "bidirectional"))
      (node (ref "U5") (pin "4") (pinfunction "1S_4") (pintype "bidirectional"))
    )
    (net (code "40") (name "Net-(U2-PROG)") (class "Default")
      (node (ref "R7") (pin "1") (pinfunction "1_1") (pintype "passive"))
      (node (ref "U2") (pin "5") (pinfunction "PROG_5") (pintype "input"))
    )
    (net (code "41") (name "Net-(U4-AVDD)") (class "Default")
      (node (ref "C13") (pin "1") (pinfunction "1_1") (pintype "passive"))
      (node (ref "U4") (pin "60") (pinfunction "AVDD_60") (pintype "bidirectional"))
    )
    (net (code "42") (name "Net-(U4-PG0(DIG3))") (class "Default")
      (node (ref "D6") (pin "A2") (pinfunction "A2_A2") (pintype "passive"))
      (node (ref "U4") (pin "14") (pinfunction "PG0(DIG3)_14") (pintype "bidirectional"))
    )
    (net (code "43") (name "Net-(U4-PG1(DIG1))") (class "Default")
      (node (ref "D6") (pin "A1") (pinfunction "A1_A1") (pintype "passive"))
      (node (ref "U4") (pin "15") (pinfunction "PG1(DIG1)_15") (pintype "bidirectional"))
    )
    (net (code "44") (name "Net-(U4-XTAL1)") (class "Default")
      (node (ref "C14") (pin "1") (pinfunction "1_1") (pintype "passive"))
      (node (ref "U4") (pin "57") (pinfunction "XTAL1_57") (pintype "bidirectional"))
      (node (ref "Y1") (pin "3") (pinfunction "2_3") (pintype "passive"))
    )
    (net (code "45") (name "Net-(U4-XTAL2)") (class "Default")
      (node (ref "C15") (pin "1") (pinfunction "1_1") (pintype "passive"))
      (node (ref "U4") (pin "56") (pinfunction "XTAL2_56") (pintype "bidirectional"))
      (node (ref "Y1") (pin "1") (pinfunction "1_1") (pintype "passive"))
    )
    (net (code "46") (name "PITCH") (class "Default")
      (node (ref "J3") (pin "V") (pinfunction "V_V") (pintype "bidirectional"))
      (node (ref "J8") (pin "V") (pinfunction "V_V") (pintype "bidirectional"))
      (node (ref "U4") (pin "2") (pinfunction "PF3(ADC3/DIG4)_2") (pintype "bidirectional"))
    )
    (net (code "47") (name "RESET") (class "Default")
      (node (ref "B1") (pin "1") (pinfunction "1_1") (pintype "passive"))
      (node (ref "B1") (pin "2") (pinfunction "1_2") (pintype "passive"))
      (node (ref "C1") (pin "1") (pinfunction "1_1") (pintype "passive"))
      (node (ref "J4") (pin "5") (pinfunction "5_5") (pintype "passive"))
      (node (ref "R2") (pin "1") (pinfunction "1_1") (pintype "passive"))
      (node (ref "U4") (pin "12") (pinfunction "RSTN_12") (pintype "bidirectional"))
    )
    (net (code "48") (name "RF") (class "Default")
      (node (ref "D4") (pin "A1") (pinfunction "A1_A1") (pintype "passive"))
      (node (ref "U4") (pin "16") (pinfunction "PG2(AMR)_16") (pintype "bidirectional"))
    )
    (net (code "49") (name "ROLL") (class "Default")
      (node (ref "J3") (pin "H") (pinfunction "H_H") (pintype "bidirectional"))
      (node (ref "J8") (pin "H") (pinfunction "H_H") (pintype "bidirectional"))
      (node (ref "U4") (pin "1") (pinfunction "PF2(ADC2/DIG2)_1") (pintype "bidirectional"))
    )
    (net (code "50") (name "RXI") (class "Default")
      (node (ref "U3") (pin "5") (pinfunction "RXD_5") (pintype "input"))
      (node (ref "U5") (pin "10") (pinfunction "3Z_10") (pintype "bidirectional"))
    )
    (net (code "51") (name "RXI-0") (class "Default")
      (node (ref "U4") (pin "47") (pinfunction "PE1(TXD0)_47") (pintype "bidirectional"))
      (node (ref "U5") (pin "11") (pinfunction "3Y0_11") (pintype "bidirectional"))
    )
    (net (code "52") (name "RXI-1") (class "Default")
      (node (ref "JP1") (pin "CTS") (pinfunction "2_CTS") (pintype "passive"))
      (node (ref "U5") (pin "9") (pinfunction "3Y1_9") (pintype "bidirectional"))
    )
    (net (code "53") (name "RXLED") (class "Default")
      (node (ref "D5") (pin "C2") (pinfunction "C2_C2") (pintype "passive"))
      (node (ref "U3") (pin "22") (pinfunction "RXLED_22") (pintype "input"))
    )
    (net (code "54") (name "SCK") (class "Default")
      (node (ref "J4") (pin "3") (pinfunction "3_3") (pintype "passive"))
      (node (ref "U4") (pin "37") (pinfunction "PB1(SCK/PCINT1)_37") (pintype "bidirectional"))
    )
    (net (code "55") (name "SHIELD") (class "Default")
      (node (ref "B12") (pin "P2") (pinfunction "P2_P2") (pintype "bidirectional"))
    )
    (net (code "56") (name "THROTTLE") (class "Default")
      (node (ref "J2") (pin "V") (pinfunction "V_V") (pintype "bidirectional"))
      (node (ref "J7") (pin "V") (pinfunction "V_V") (pintype "bidirectional"))
      (node (ref "U4") (pin "64") (pinfunction "PF1(ADC1)_64") (pintype "bidirectional"))
    )
    (net (code "57") (name "TXLED") (class "Default")
      (node (ref "D5") (pin "C1") (pinfunction "C1_C1") (pintype "passive"))
      (node (ref "U3") (pin "23") (pinfunction "TXLED_23") (pintype "input"))
    )
    (net (code "58") (name "TXO") (class "Default")
      (node (ref "U3") (pin "1") (pinfunction "TXD_1") (pintype "output"))
      (node (ref "U5") (pin "6") (pinfunction "2Z_6") (pintype "bidirectional"))
    )
    (net (code "59") (name "TXO-0") (class "Default")
      (node (ref "U4") (pin "46") (pinfunction "PE0(RXD0/PCINT8)_46") (pintype "bidirectional"))
      (node (ref "U5") (pin "7") (pinfunction "2Y0_7") (pintype "bidirectional"))
    )
    (net (code "60") (name "TXO-1") (class "Default")
      (node (ref "JP1") (pin "VCC") (pinfunction "3_VCC") (pintype "passive"))
      (node (ref "U5") (pin "5") (pinfunction "2Y1_5") (pintype "bidirectional"))
    )
    (net (code "61") (name "USB_D_N") (class "Default")
      (node (ref "J1") (pin "2") (pinfunction "2-D-_2") (pintype "bidirectional"))
      (node (ref "U3") (pin "16") (pinfunction "USBDM_16") (pintype "bidirectional"))
    )
    (net (code "62") (name "USB_D_P") (class "Default")
      (node (ref "J1") (pin "3") (pinfunction "3-D+_3") (pintype "bidirectional"))
      (node (ref "U3") (pin "15") (pinfunction "USBDP_15") (pintype "bidirectional"))
    )
    (net (code "63") (name "VBAT") (class "Default")
      (node (ref "D2") (pin "C") (pinfunction "C_C") (pintype "passive"))
      (node (ref "D3") (pin "C") (pinfunction "C_C") (pintype "passive"))
      (node (ref "P2") (pin "T") (pinfunction "T_T") (pintype "bidirectional"))
      (node (ref "S1") (pin "2") (pinfunction "C_2") (pintype "bidirectional"))
    )
    (net (code "64") (name "VBUS") (class "Default")
      (node (ref "C5") (pin "1") (pinfunction "1_1") (pintype "passive"))
      (node (ref "D1") (pin "A2") (pinfunction "A2_A2") (pintype "passive"))
      (node (ref "D2") (pin "A") (pinfunction "A_A") (pintype "passive"))
      (node (ref "J1") (pin "1") (pinfunction "1-VCC_1") (pintype "bidirectional"))
      (node (ref "P1") (pin "T") (pinfunction "T_T") (pintype "bidirectional"))
      (node (ref "U2") (pin "4") (pinfunction "VDD_4") (pintype "power_in"))
      (node (ref "V1") (pin "P1") (pinfunction "N_P1") (pintype "bidirectional"))
      (node (ref "V2") (pin "P1") (pinfunction "N_P1") (pintype "bidirectional"))
      (node (ref "V23") (pin "P1") (pinfunction "N_P1") (pintype "bidirectional"))
      (node (ref "V24") (pin "P1") (pinfunction "N_P1") (pintype "bidirectional"))
      (node (ref "V26") (pin "P1") (pinfunction "N_P1") (pintype "bidirectional"))
      (node (ref "V27") (pin "P1") (pinfunction "N_P1") (pintype "bidirectional"))
      (node (ref "V28") (pin "P1") (pinfunction "N_P1") (pintype "bidirectional"))
    )
    (net (code "65") (name "VREG_IN") (class "Default")
      (node (ref "C7") (pin "1") (pinfunction "1_1") (pintype "passive"))
      (node (ref "C8") (pin "1") (pinfunction "1_1") (pintype "passive"))
      (node (ref "L1") (pin "RAW") (pinfunction "VIN_RAW") (pintype "bidirectional"))
      (node (ref "S1") (pin "1") (pinfunction "ON_1") (pintype "bidirectional"))
      (node (ref "U3") (pin "20") (pinfunction "VCC_20") (pintype "power_in"))
    )
    (net (code "66") (name "YAW") (class "Default")
      (node (ref "J2") (pin "H") (pinfunction "H_H") (pintype "bidirectional"))
      (node (ref "J7") (pin "H") (pinfunction "H_H") (pintype "bidirectional"))
      (node (ref "U4") (pin "63") (pinfunction "PF0(ADC0)_63") (pintype "bidirectional"))
    )
    (net (code "67") (name "unconnected-(J1-4-ID-Pad4)") (class "Default")
      (node (ref "J1") (pin "4") (pinfunction "4-ID_4") (pintype "bidirectional"))
    )
    (net (code "68") (name "unconnected-(L1-PadSCK)") (class "Default")
      (node (ref "L1") (pin "SCK") (pinfunction "SCK_SCK") (pintype "bidirectional"))
    )
    (net (code "69") (name "unconnected-(L1-PadSDI)") (class "Default")
      (node (ref "L1") (pin "SDI") (pinfunction "SDI_SDI") (pintype "bidirectional"))
    )
    (net (code "70") (name "unconnected-(L1-PadSDO)") (class "Default")
      (node (ref "L1") (pin "SDO") (pinfunction "SDO_SDO") (pintype "bidirectional"))
    )
    (net (code "71") (name "unconnected-(L1-Pad{slash}CS)") (class "Default")
      (node (ref "L1") (pin "/CS") (pinfunction "/CS_/CS") (pintype "bidirectional"))
    )
    (net (code "72") (name "unconnected-(L1-SCL-PadCL)") (class "Default")
      (node (ref "L1") (pin "CL") (pinfunction "SCL_CL") (pintype "bidirectional"))
    )
    (net (code "73") (name "unconnected-(L1-SDA-PadDA)") (class "Default")
      (node (ref "L1") (pin "DA") (pinfunction "SDA_DA") (pintype "bidirectional"))
    )
    (net (code "74") (name "unconnected-(S1-OFF-Pad3)") (class "Default")
      (node (ref "S1") (pin "3") (pinfunction "OFF_3") (pintype "bidirectional"))
    )
    (net (code "75") (name "unconnected-(U3-DCD-Pad10)") (class "Default")
      (node (ref "U3") (pin "10") (pinfunction "DCD_10") (pintype "input"))
    )
    (net (code "76") (name "unconnected-(U3-DSR-Pad9)") (class "Default")
      (node (ref "U3") (pin "9") (pinfunction "DSR_9") (pintype "input"))
    )
    (net (code "77") (name "unconnected-(U3-OSCI-Pad27)") (class "Default")
      (node (ref "U3") (pin "27") (pinfunction "OSCI_27") (pintype "input"))
    )
    (net (code "78") (name "unconnected-(U3-OSCO-Pad28)") (class "Default")
      (node (ref "U3") (pin "28") (pinfunction "OSCO_28") (pintype "output"))
    )
    (net (code "79") (name "unconnected-(U3-PWREN-Pad14)") (class "Default")
      (node (ref "U3") (pin "14") (pinfunction "PWREN_14") (pintype "input"))
    )
    (net (code "80") (name "unconnected-(U3-RESET-Pad19)") (class "Default")
      (node (ref "U3") (pin "19") (pinfunction "RESET_19") (pintype "input"))
    )
    (net (code "81") (name "unconnected-(U3-RI-Pad6)") (class "Default")
      (node (ref "U3") (pin "6") (pinfunction "RI_6") (pintype "input"))
    )
    (net (code "82") (name "unconnected-(U3-RTS-Pad3)") (class "Default")
      (node (ref "U3") (pin "3") (pinfunction "RTS_3") (pintype "output"))
    )
    (net (code "83") (name "unconnected-(U3-SLEEP-Pad12)") (class "Default")
      (node (ref "U3") (pin "12") (pinfunction "SLEEP_12") (pintype "input"))
    )
    (net (code "84") (name "unconnected-(U3-TXDEN-Pad13)") (class "Default")
      (node (ref "U3") (pin "13") (pinfunction "TXDEN_13") (pintype "input"))
    )
    (net (code "85") (name "unconnected-(U4-AREF-Pad62)") (class "Default")
      (node (ref "U4") (pin "62") (pinfunction "AREF_62") (pintype "bidirectional"))
    )
    (net (code "86") (name "unconnected-(U4-PB0(SSN{slash}PCINT0)-Pad36)") (class "Default")
      (node (ref "U4") (pin "36") (pinfunction "PB0(SSN/PCINT0)_36") (pintype "bidirectional"))
    )
    (net (code "87") (name "unconnected-(U4-PB6(OC1B{slash}PCINT6)-Pad42)") (class "Default")
      (node (ref "U4") (pin "42") (pinfunction "PB6(OC1B/PCINT6)_42") (pintype "bidirectional"))
    )
    (net (code "88") (name "unconnected-(U4-PB7(OC0A{slash}OC1C{slash}PCINT7)-Pad43)") (class "Default")
      (node (ref "U4") (pin "43") (pinfunction "PB7(OC0A/OC1C/PCINT7)_43") (pintype "bidirectional"))
    )
    (net (code "89") (name "unconnected-(U4-PD4(ICP1)-Pad29)") (class "Default")
      (node (ref "U4") (pin "29") (pinfunction "PD4(ICP1)_29") (pintype "bidirectional"))
    )
    (net (code "90") (name "unconnected-(U4-PD5(XCK1)-Pad30)") (class "Default")
      (node (ref "U4") (pin "30") (pinfunction "PD5(XCK1)_30") (pintype "bidirectional"))
    )
    (net (code "91") (name "unconnected-(U4-PE2(XCK0{slash}AIN0)-Pad48)") (class "Default")
      (node (ref "U4") (pin "48") (pinfunction "PE2(XCK0/AIN0)_48") (pintype "bidirectional"))
    )
    (net (code "92") (name "unconnected-(U4-PE3(OC3A{slash}AIN1)-Pad49)") (class "Default")
      (node (ref "U4") (pin "49") (pinfunction "PE3(OC3A/AIN1)_49") (pintype "bidirectional"))
    )
    (net (code "93") (name "unconnected-(U4-PF4(ADC4{slash}TCK)-Pad3)") (class "Default")
      (node (ref "U4") (pin "3") (pinfunction "PF4(ADC4/TCK)_3") (pintype "bidirectional"))
    )
    (net (code "94") (name "unconnected-(U4-PF5(ADC5{slash}TMS)-Pad4)") (class "Default")
      (node (ref "U4") (pin "4") (pinfunction "PF5(ADC5/TMS)_4") (pintype "bidirectional"))
    )
    (net (code "95") (name "unconnected-(U4-PF6(ADC6{slash}TDO)-Pad5)") (class "Default")
      (node (ref "U4") (pin "5") (pinfunction "PF6(ADC6/TDO)_5") (pintype "bidirectional"))
    )
    (net (code "96") (name "unconnected-(U4-PF7(ADC7{slash}TDI)-Pad6)") (class "Default")
      (node (ref "U4") (pin "6") (pinfunction "PF7(ADC7/TDI)_6") (pintype "bidirectional"))
    )
    (net (code "97") (name "unconnected-(U4-PG3(TOSC2)-Pad17)") (class "Default")
      (node (ref "U4") (pin "17") (pinfunction "PG3(TOSC2)_17") (pintype "bidirectional"))
    )
    (net (code "98") (name "unconnected-(U4-PG4(TOSC1)-Pad18)") (class "Default")
      (node (ref "U4") (pin "18") (pinfunction "PG4(TOSC1)_18") (pintype "bidirectional"))
    )
    (net (code "99") (name "unconnected-(U4-PG5(OC0B)-Pad19)") (class "Default")
      (node (ref "U4") (pin "19") (pinfunction "PG5(OC0B)_19") (pintype "bidirectional"))
    )
    (net (code "100") (name "unconnected-(U4-RSTON-Pad13)") (class "Default")
      (node (ref "U4") (pin "13") (pinfunction "RSTON_13") (pintype "bidirectional"))
    )
  )
)
